# ESP32_Module.net
KiCad netlist of a schematic drawn in Altium Designer
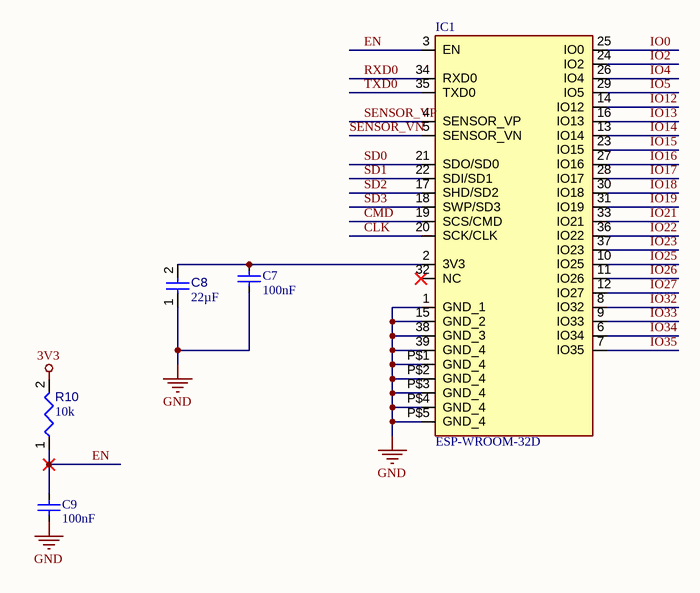
[diagram p0: ESP32_Module.SchDoc]

(export (version "E")
  (design (tool "Eeschema 10.0.6"))
  (components
    (comp (ref "C7")
      (value "100nF")
      (footprint "0603C_L")
      (fields
        (field (name "MANUFACTURER") "Yageo")
        (field (name "MANUFACTURER PART NUMBER") "CC0603ZRY5V9BB104")
        (field (name "Comment") "Cap100nF_50V_0603")
        (field (name "SOURCE") "WCT.SCHLIB")
      )
      (libsource (lib "Kylian Siemou Diemou Tchoya") (part "Cap100nF_50V_0603"))
    )
    (comp (ref "C8")
      (value "22µF")
      (footprint "CAPC0805(2012)145_L")
      (description "Chip Capacitor, 22µF +/-40%, 16V, 0805, Thickness 1.45 mm")
      (fields (field (name "TOLERANCE") "5%") (field (name "Comment") "Capacitor 22µF +/-40% 16V 0805"))
      (libsource (lib "Kylian Siemou Diemou Tchoya") (part "CAP-NP-2"))
    )
    (comp (ref "C9")
      (value "100nF")
      (footprint "0603C_L")
      (fields
        (field (name "MANUFACTURER") "Yageo")
        (field (name "MANUFACTURER PART NUMBER") "CC0603ZRY5V9BB104")
        (field (name "Comment") "Cap100nF_50V_0603")
        (field (name "SOURCE") "WCT.SCHLIB")
      )
      (libsource (lib "Kylian Siemou Diemou Tchoya") (part "Cap100nF_50V_0603"))
    )
    (comp (ref "IC1")
      (value "ESP-WROOM-32D")
      (footprint "ESPWROOM32D")
      (description "WiFi / 802.11 Modules")
      (fields (field (name "MF") "Espressif Systems"))
      (libsource (lib "ESP-WROOM-32D") (part "ESP-WROOM-32D"))
    )
    (comp (ref "R10")
      (value "10k")
      (footprint "RESC0402(1005)_L")
      (description "Chip Resistor, 10 kOhms, +/-1 %, 63 mW, -55 to 125 degC, 0402")
      (fields (field (name "POWER") "63mW") (field (name "TOLERANCE") "1%"))
      (libsource (lib "Kylian Siemou Diemou Tchoya") (part "RES-2"))
    )
  )
  (nets
    (net (code "1") (name "/CLK") (class "Default")
      (node (ref "IC1") (pin "20") (pinfunction "SCK/CLK_20") (pintype "bidirectional"))
    )
    (net (code "2") (name "/CMD") (class "Default")
      (node (ref "IC1") (pin "19") (pinfunction "SCS/CMD_19") (pintype "bidirectional"))
    )
    (net (code "3") (name "/EN") (class "Default")
      (node (ref "C9") (pin "2") (pinfunction "2_2") (pintype "passive"))
      (node (ref "IC1") (pin "3") (pinfunction "EN_3") (pintype "bidirectional"))
      (node (ref "R10") (pin "1") (pinfunction "1_1") (pintype "passive"))
    )
    (net (code "4") (name "/IO0") (class "Default")
      (node (ref "IC1") (pin "25") (pinfunction "IO0_25") (pintype "bidirectional"))
    )
    (net (code "5") (name "/IO2") (class "Default")
      (node (ref "IC1") (pin "24") (pinfunction "IO2_24") (pintype "bidirectional"))
    )
    (net (code "6") (name "/IO4") (class "Default")
      (node (ref "IC1") (pin "26") (pinfunction "IO4_26") (pintype "bidirectional"))
    )
    (net (code "7") (name "/IO5") (class "Default")
      (node (ref "IC1") (pin "29") (pinfunction "IO5_29") (pintype "bidirectional"))
    )
    (net (code "8") (name "/IO12") (class "Default")
      (node (ref "IC1") (pin "14") (pinfunction "IO12_14") (pintype "bidirectional"))
    )
    (net (code "9") (name "/IO13") (class "Default")
      (node (ref "IC1") (pin "16") (pinfunction "IO13_16") (pintype "bidirectional"))
    )
    (net (code "10") (name "/IO14") (class "Default")
      (node (ref "IC1") (pin "13") (pinfunction "IO14_13") (pintype "bidirectional"))
    )
    (net (code "11") (name "/IO15") (class "Default")
      (node (ref "IC1") (pin "23") (pinfunction "IO15_23") (pintype "bidirectional"))
    )
    (net (code "12") (name "/IO16") (class "Default")
      (node (ref "IC1") (pin "27") (pinfunction "IO16_27") (pintype "bidirectional"))
    )
    (net (code "13") (name "/IO17") (class "Default")
      (node (ref "IC1") (pin "28") (pinfunction "IO17_28") (pintype "bidirectional"))
    )
    (net (code "14") (name "/IO18") (class "Default")
      (node (ref "IC1") (pin "30") (pinfunction "IO18_30") (pintype "bidirectional"))
    )
    (net (code "15") (name "/IO19") (class "Default")
      (node (ref "IC1") (pin "31") (pinfunction "IO19_31") (pintype "bidirectional"))
    )
    (net (code "16") (name "/IO21") (class "Default")
      (node (ref "IC1") (pin "33") (pinfunction "IO21_33") (pintype "bidirectional"))
    )
    (net (code "17") (name "/IO22") (class "Default")
      (node (ref "IC1") (pin "36") (pinfunction "IO22_36") (pintype "bidirectional"))
    )
    (net (code "18") (name "/IO23") (class "Default")
      (node (ref "IC1") (pin "37") (pinfunction "IO23_37") (pintype "bidirectional"))
    )
    (net (code "19") (name "/IO25") (class "Default")
      (node (ref "IC1") (pin "10") (pinfunction "IO25_10") (pintype "bidirectional"))
    )
    (net (code "20") (name "/IO26") (class "Default")
      (node (ref "IC1") (pin "11") (pinfunction "IO26_11") (pintype "bidirectional"))
    )
    (net (code "21") (name "/IO27") (class "Default")
      (node (ref "IC1") (pin "12") (pinfunction "IO27_12") (pintype "bidirectional"))
    )
    (net (code "22") (name "/IO32") (class "Default")
      (node (ref "IC1") (pin "8") (pinfunction "IO32_8") (pintype "bidirectional"))
    )
    (net (code "23") (name "/IO33") (class "Default")
      (node (ref "IC1") (pin "9") (pinfunction "IO33_9") (pintype "bidirectional"))
    )
    (net (code "24") (name "/IO34") (class "Default")
      (node (ref "IC1") (pin "6") (pinfunction "IO34_6") (pintype "bidirectional"))
    )
    (net (code "25") (name "/IO35") (class "Default")
      (node (ref "IC1") (pin "7") (pinfunction "IO35_7") (pintype "bidirectional"))
    )
    (net (code "26") (name "/RXD0") (class "Default")
      (node (ref "IC1") (pin "34") (pinfunction "RXD0_34") (pintype "bidirectional"))
    )
    (net (code "27") (name "/SD0") (class "Default")
      (node (ref "IC1") (pin "21") (pinfunction "SDO/SD0_21") (pintype "bidirectional"))
    )
    (net (code "28") (name "/SD1") (class "Default")
      (node (ref "IC1") (pin "22") (pinfunction "SDI/SD1_22") (pintype "bidirectional"))
    )
    (net (code "29") (name "/SD2") (class "Default")
      (node (ref "IC1") (pin "17") (pinfunction "SHD/SD2_17") (pintype "bidirectional"))
    )
    (net (code "30") (name "/SD3") (class "Default")
      (node (ref "IC1") (pin "18") (pinfunction "SWP/SD3_18") (pintype "bidirectional"))
    )
    (net (code "31") (name "/SENSOR_VN") (class "Default")
      (node (ref "IC1") (pin "5") (pinfunction "SENSOR_VN_5") (pintype "bidirectional"))
    )
    (net (code "32") (name "/SENSOR_VP") (class "Default")
      (node (ref "IC1") (pin "4") (pinfunction "SENSOR_VP_4") (pintype "bidirectional"))
    )
    (net (code "33") (name "/TXD0") (class "Default")
      (node (ref "IC1") (pin "35") (pinfunction "TXD0_35") (pintype "bidirectional"))
    )
    (net (code "34") (name "3V3") (class "Default")
      (node (ref "R10") (pin "2") (pinfunction "2_2") (pintype "passive"))
    )
    (net (code "35") (name "GND") (class "Default")
      (node (ref "C7") (pin "1") (pinfunction "1_1") (pintype "passive"))
      (node (ref "C8") (pin "1") (pinfunction "1_1") (pintype "passive"))
      (node (ref "C9") (pin "1") (pinfunction "1_1") (pintype "passive"))
      (node (ref "IC1") (pin "1") (pinfunction "GND_1_1") (pintype "bidirectional"))
      (node (ref "IC1") (pin "15") (pinfunction "GND_2_15") (pintype "bidirectional"))
      (node (ref "IC1") (pin "38") (pinfunction "GND_3_38") (pintype "bidirectional"))
      (node (ref "IC1") (pin "39") (pinfunction "GND_4_39") (pintype "bidirectional"))
      (node (ref "IC1") (pin "P$1") (pinfunction "GND_4_P$1") (pintype "bidirectional"))
      (node (ref "IC1") (pin "P$2") (pinfunction "GND_4_P$2") (pintype "bidirectional"))
      (node (ref "IC1") (pin "P$3") (pinfunction "GND_4_P$3") (pintype "bidirectional"))
      (node (ref "IC1") (pin "P$4") (pinfunction "GND_4_P$4") (pintype "bidirectional"))
      (node (ref "IC1") (pin "P$5") (pinfunction "GND_4_P$5") (pintype "bidirectional"))
    )
    (net (code "36") (name "Net-(IC1-3V3)") (class "Default")
      (node (ref "C7") (pin "2") (pinfunction "2_2") (pintype "passive"))
      (node (ref "C8") (pin "2") (pinfunction "2_2") (pintype "passive"))
      (node (ref "IC1") (pin "2") (pinfunction "3V3_2") (pintype "bidirectional"))
    )
    (net (code "37") (name "unconnected-(IC1-NC-Pad32)") (class "Default")
      (node (ref "IC1") (pin "32") (pinfunction "NC_32") (pintype "passive+no_connect"))
    )
  )
)
